# FT230X_Breakout.net
KiCad netlist of a schematic drawn in EAGLE
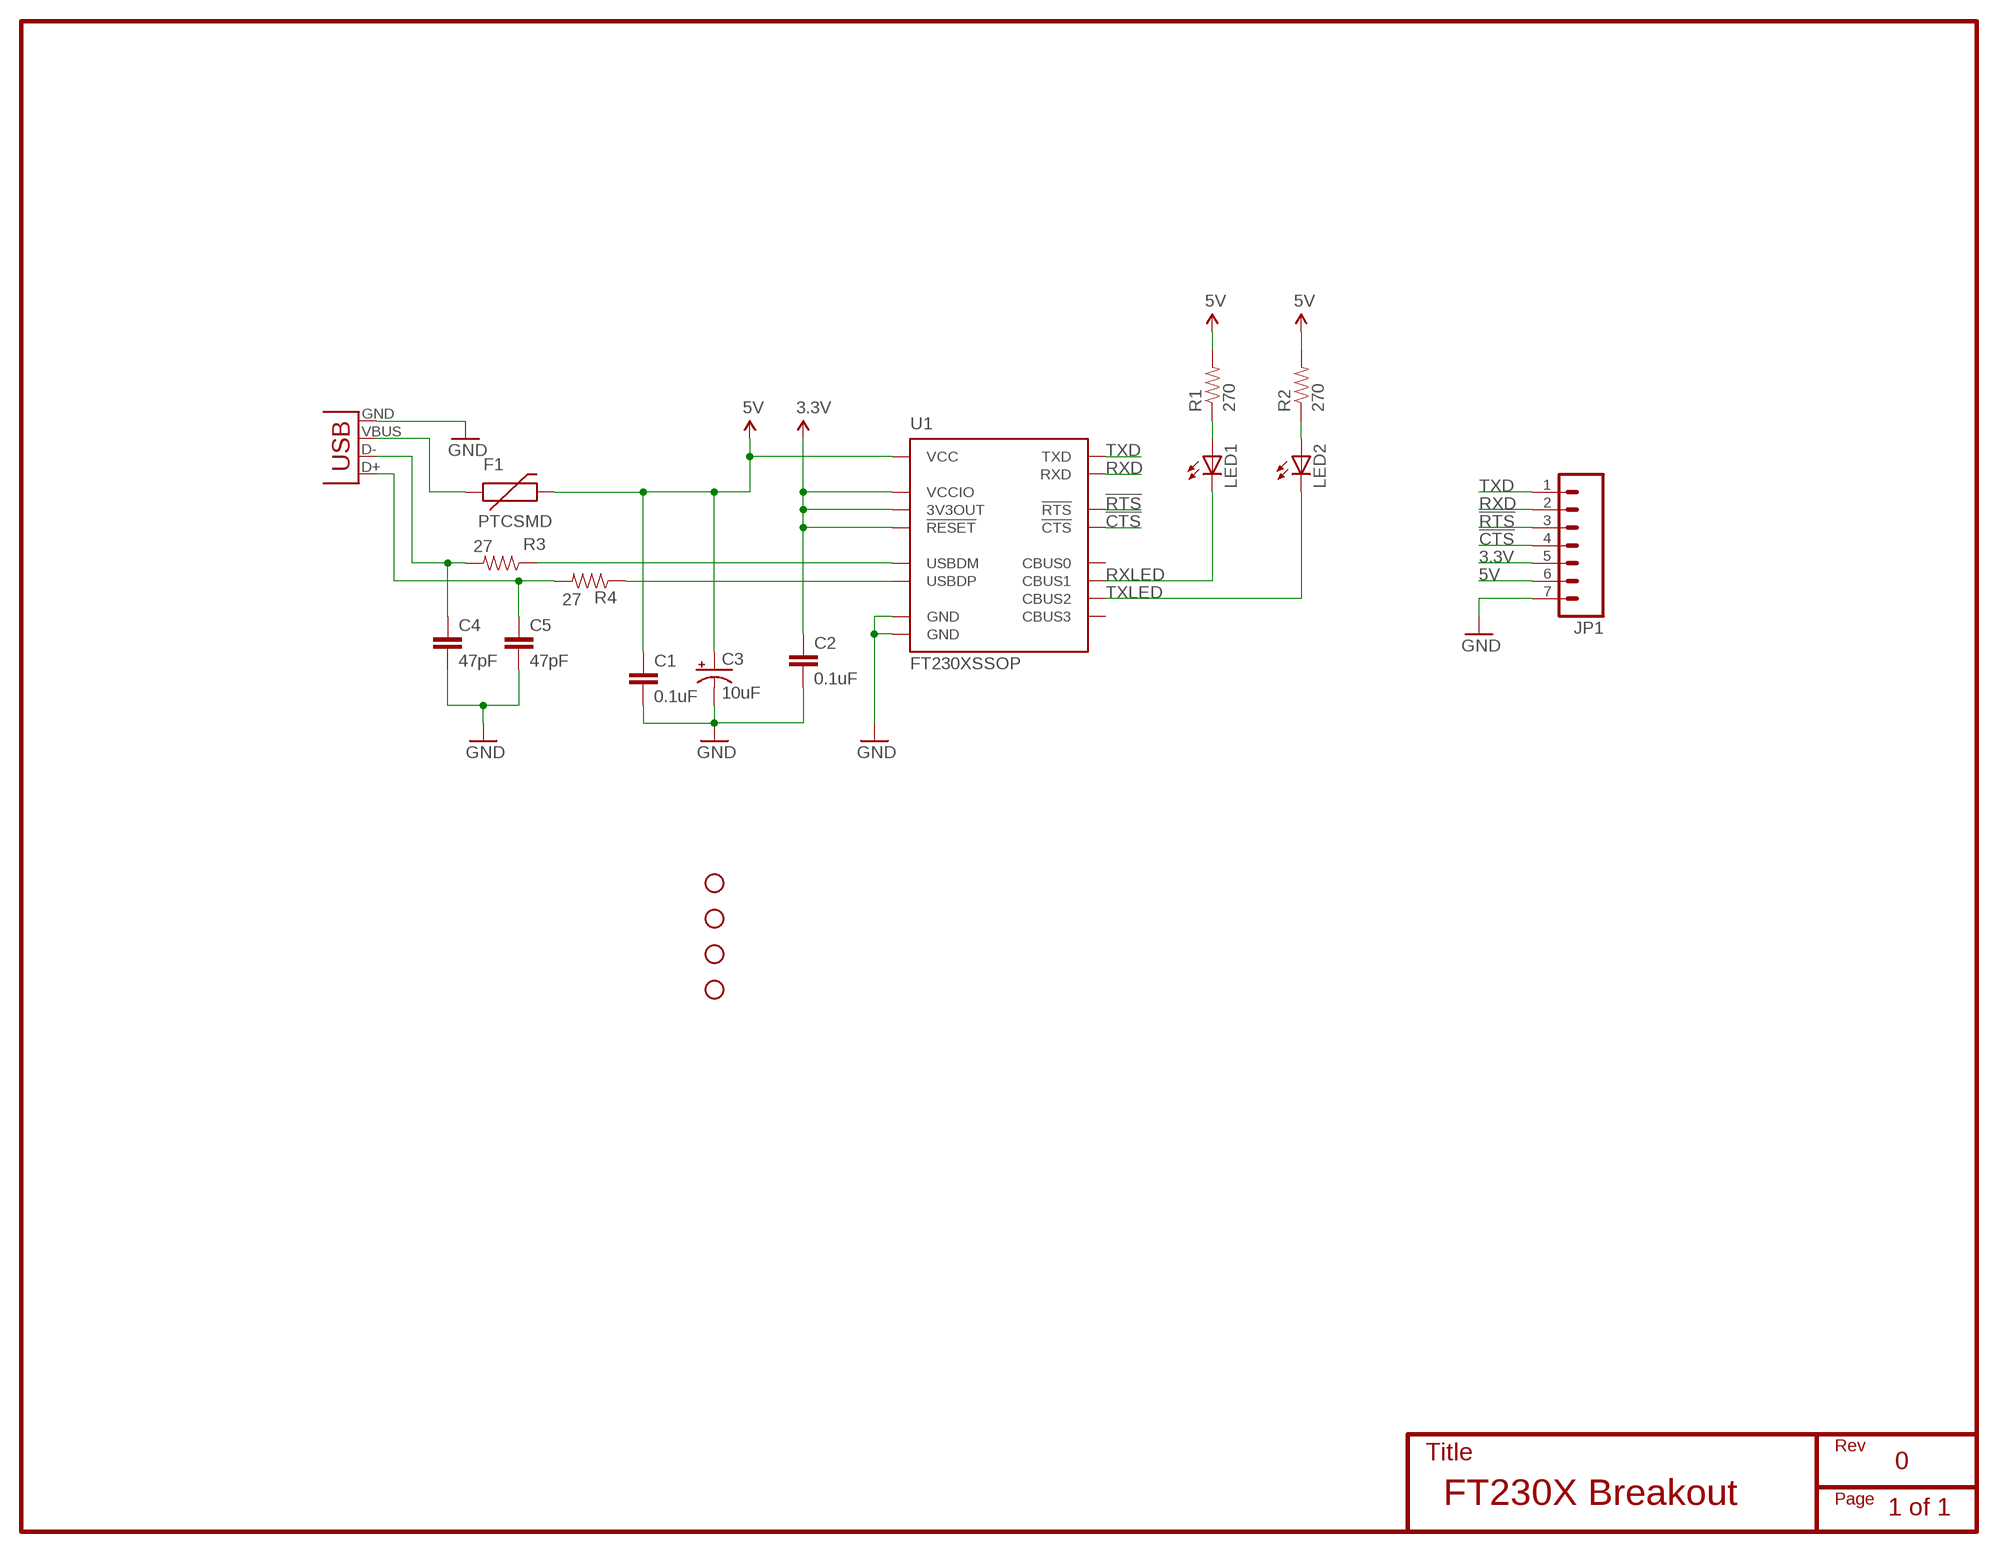
[diagram p0: schematic, sheet 1]

(export (version "E")
  (design (tool "Eeschema 10.0.6"))
  (components
    (comp (ref "C1")
      (value "0.1uF")
      (footprint "eagle-import:0603-CAP")
      (libsource (lib "eagle-import") (part "CAP0603-CAP"))
    )
    (comp (ref "C2")
      (value "0.1uF")
      (footprint "eagle-import:0603-CAP")
      (libsource (lib "eagle-import") (part "CAP0603-CAP"))
    )
    (comp (ref "C3")
      (value "10uF")
      (footprint "eagle-import:EIA3216-KIT")
      (libsource (lib "eagle-import") (part "CAP_POL1206-KIT"))
    )
    (comp (ref "C4")
      (value "47pF")
      (footprint "eagle-import:0603-CAP")
      (libsource (lib "eagle-import") (part "CAP0603-CAP"))
    )
    (comp (ref "C5")
      (value "47pF")
      (footprint "eagle-import:0603-CAP")
      (libsource (lib "eagle-import") (part "CAP0603-CAP"))
    )
    (comp (ref "F1")
      (value "PTCSMD")
      (footprint "eagle-import:PTC-1206")
      (libsource (lib "eagle-import") (part "PTCSMD"))
    )
    (comp (ref "JP1")
      (value "M07")
      (footprint "eagle-import:1X07")
      (libsource (lib "eagle-import") (part "M07"))
    )
    (comp (ref "JP2")
      (value "USBSMD")
      (footprint "eagle-import:USB-MINIB")
      (libsource (lib "eagle-import") (part "USBSMD"))
    )
    (comp (ref "LED1")
      (value "LED0603")
      (footprint "eagle-import:LED-0603")
      (libsource (lib "eagle-import") (part "LED0603"))
    )
    (comp (ref "LED2")
      (value "LED0603")
      (footprint "eagle-import:LED-0603")
      (libsource (lib "eagle-import") (part "LED0603"))
    )
    (comp (ref "R1")
      (value "270")
      (footprint "eagle-import:0603-RES")
      (libsource (lib "eagle-import") (part "RESISTOR0603-RES"))
    )
    (comp (ref "R2")
      (value "270")
      (footprint "eagle-import:0603-RES")
      (libsource (lib "eagle-import") (part "RESISTOR0603-RES"))
    )
    (comp (ref "R3")
      (value "27")
      (footprint "eagle-import:0603-RES")
      (libsource (lib "eagle-import") (part "RESISTOR0603-RES"))
    )
    (comp (ref "R4")
      (value "27")
      (footprint "eagle-import:0603-RES")
      (libsource (lib "eagle-import") (part "RESISTOR0603-RES"))
    )
    (comp (ref "STANDOFF1")
      (value "STAND-OFF")
      (footprint "eagle-import:STAND-OFF")
      (libsource (lib "eagle-import") (part "STAND-OFF"))
    )
    (comp (ref "STANDOFF2")
      (value "STAND-OFF")
      (footprint "eagle-import:STAND-OFF")
      (libsource (lib "eagle-import") (part "STAND-OFF"))
    )
    (comp (ref "STANDOFF3")
      (value "STAND-OFF")
      (footprint "eagle-import:STAND-OFF")
      (libsource (lib "eagle-import") (part "STAND-OFF"))
    )
    (comp (ref "STANDOFF4")
      (value "STAND-OFF")
      (footprint "eagle-import:STAND-OFF")
      (libsource (lib "eagle-import") (part "STAND-OFF"))
    )
    (comp (ref "U1")
      (value "FT230XSSOP")
      (footprint "eagle-import:SSOP16")
      (libsource (lib "eagle-import") (part "FT230XSSOP"))
    )
  )
  (nets
    (net (code "1") (name "/RXD") (class "Default")
      (node (ref "JP1") (pin "2") (pinfunction "2_2") (pintype "passive"))
      (node (ref "U1") (pin "4") (pinfunction "RXD_4") (pintype "input"))
    )
    (net (code "2") (name "/RXLED") (class "Default")
      (node (ref "LED1") (pin "C") (pinfunction "C_C") (pintype "passive"))
      (node (ref "U1") (pin "14") (pinfunction "CBUS1_14") (pintype "bidirectional"))
    )
    (net (code "3") (name "/TXD") (class "Default")
      (node (ref "JP1") (pin "1") (pinfunction "1_1") (pintype "passive"))
      (node (ref "U1") (pin "1") (pinfunction "TXD_1") (pintype "output"))
    )
    (net (code "4") (name "/TXLED") (class "Default")
      (node (ref "LED2") (pin "C") (pinfunction "C_C") (pintype "passive"))
      (node (ref "U1") (pin "7") (pinfunction "CBUS2_7") (pintype "bidirectional"))
    )
    (net (code "5") (name "/~{CTS}") (class "Default")
      (node (ref "JP1") (pin "4") (pinfunction "4_4") (pintype "passive"))
      (node (ref "U1") (pin "6") (pinfunction "~{CTS}_6") (pintype "input"))
    )
    (net (code "6") (name "/~{RTS}") (class "Default")
      (node (ref "JP1") (pin "3") (pinfunction "3_3") (pintype "passive"))
      (node (ref "U1") (pin "2") (pinfunction "~{RTS}_2") (pintype "output"))
    )
    (net (code "7") (name "3.3V") (class "Default")
      (node (ref "C2") (pin "1") (pinfunction "1_1") (pintype "passive"))
      (node (ref "JP1") (pin "5") (pinfunction "5_5") (pintype "passive"))
      (node (ref "U1") (pin "10") (pinfunction "3V3OUT_10") (pintype "power_in"))
      (node (ref "U1") (pin "11") (pinfunction "~{RESET}_11") (pintype "input"))
      (node (ref "U1") (pin "3") (pinfunction "VCCIO_3") (pintype "power_in"))
    )
    (net (code "8") (name "5V") (class "Default")
      (node (ref "C1") (pin "1") (pinfunction "1_1") (pintype "passive"))
      (node (ref "C3") (pin "A") (pinfunction "+_A") (pintype "passive"))
      (node (ref "F1") (pin "2") (pinfunction "2_2") (pintype "bidirectional"))
      (node (ref "JP1") (pin "6") (pinfunction "6_6") (pintype "passive"))
      (node (ref "R1") (pin "2") (pinfunction "2_2") (pintype "passive"))
      (node (ref "R2") (pin "2") (pinfunction "2_2") (pintype "passive"))
      (node (ref "U1") (pin "12") (pinfunction "VCC_12") (pintype "power_in"))
    )
    (net (code "9") (name "GND") (class "Default")
      (node (ref "C1") (pin "2") (pinfunction "2_2") (pintype "passive"))
      (node (ref "C2") (pin "2") (pinfunction "2_2") (pintype "passive"))
      (node (ref "C3") (pin "C") (pinfunction "-_C") (pintype "passive"))
      (node (ref "C4") (pin "2") (pinfunction "2_2") (pintype "passive"))
      (node (ref "C5") (pin "2") (pinfunction "2_2") (pintype "passive"))
      (node (ref "JP1") (pin "7") (pinfunction "7_7") (pintype "passive"))
      (node (ref "JP2") (pin "GND") (pinfunction "GND_GND") (pintype "bidirectional"))
      (node (ref "U1") (pin "13") (pinfunction "GND_13") (pintype "power_in"))
      (node (ref "U1") (pin "5") (pinfunction "GND_5") (pintype "power_in"))
    )
    (net (code "10") (name "Net-(C4-Pad1)") (class "Default")
      (node (ref "C4") (pin "1") (pinfunction "1_1") (pintype "passive"))
      (node (ref "JP2") (pin "D-") (pinfunction "D-_D-") (pintype "bidirectional"))
      (node (ref "R3") (pin "2") (pinfunction "2_2") (pintype "passive"))
    )
    (net (code "11") (name "Net-(C5-Pad1)") (class "Default")
      (node (ref "C5") (pin "1") (pinfunction "1_1") (pintype "passive"))
      (node (ref "JP2") (pin "D+") (pinfunction "D+_D+") (pintype "bidirectional"))
      (node (ref "R4") (pin "2") (pinfunction "2_2") (pintype "passive"))
    )
    (net (code "12") (name "Net-(F1-Pad1)") (class "Default")
      (node (ref "F1") (pin "1") (pinfunction "1_1") (pintype "bidirectional"))
      (node (ref "JP2") (pin "VBUS") (pinfunction "VBUS_VBUS") (pintype "bidirectional"))
    )
    (net (code "13") (name "Net-(LED1-PadA)") (class "Default")
      (node (ref "LED1") (pin "A") (pinfunction "A_A") (pintype "passive"))
      (node (ref "R1") (pin "1") (pinfunction "1_1") (pintype "passive"))
    )
    (net (code "14") (name "Net-(LED2-PadA)") (class "Default")
      (node (ref "LED2") (pin "A") (pinfunction "A_A") (pintype "passive"))
      (node (ref "R2") (pin "1") (pinfunction "1_1") (pintype "passive"))
    )
    (net (code "15") (name "Net-(U1-USBDM)") (class "Default")
      (node (ref "R3") (pin "1") (pinfunction "1_1") (pintype "passive"))
      (node (ref "U1") (pin "9") (pinfunction "USBDM_9") (pintype "input"))
    )
    (net (code "16") (name "Net-(U1-USBDP)") (class "Default")
      (node (ref "R4") (pin "1") (pinfunction "1_1") (pintype "passive"))
      (node (ref "U1") (pin "8") (pinfunction "USBDP_8") (pintype "input"))
    )
    (net (code "17") (name "unconnected-(U1-CBUS0-Pad15)") (class "Default")
      (node (ref "U1") (pin "15") (pinfunction "CBUS0_15") (pintype "bidirectional"))
    )
    (net (code "18") (name "unconnected-(U1-CBUS3-Pad16)") (class "Default")
      (node (ref "U1") (pin "16") (pinfunction "CBUS3_16") (pintype "bidirectional"))
    )
  )
)
